# lab2_sokolov_boost.net
KiCad netlist of a schematic drawn in Altium Designer
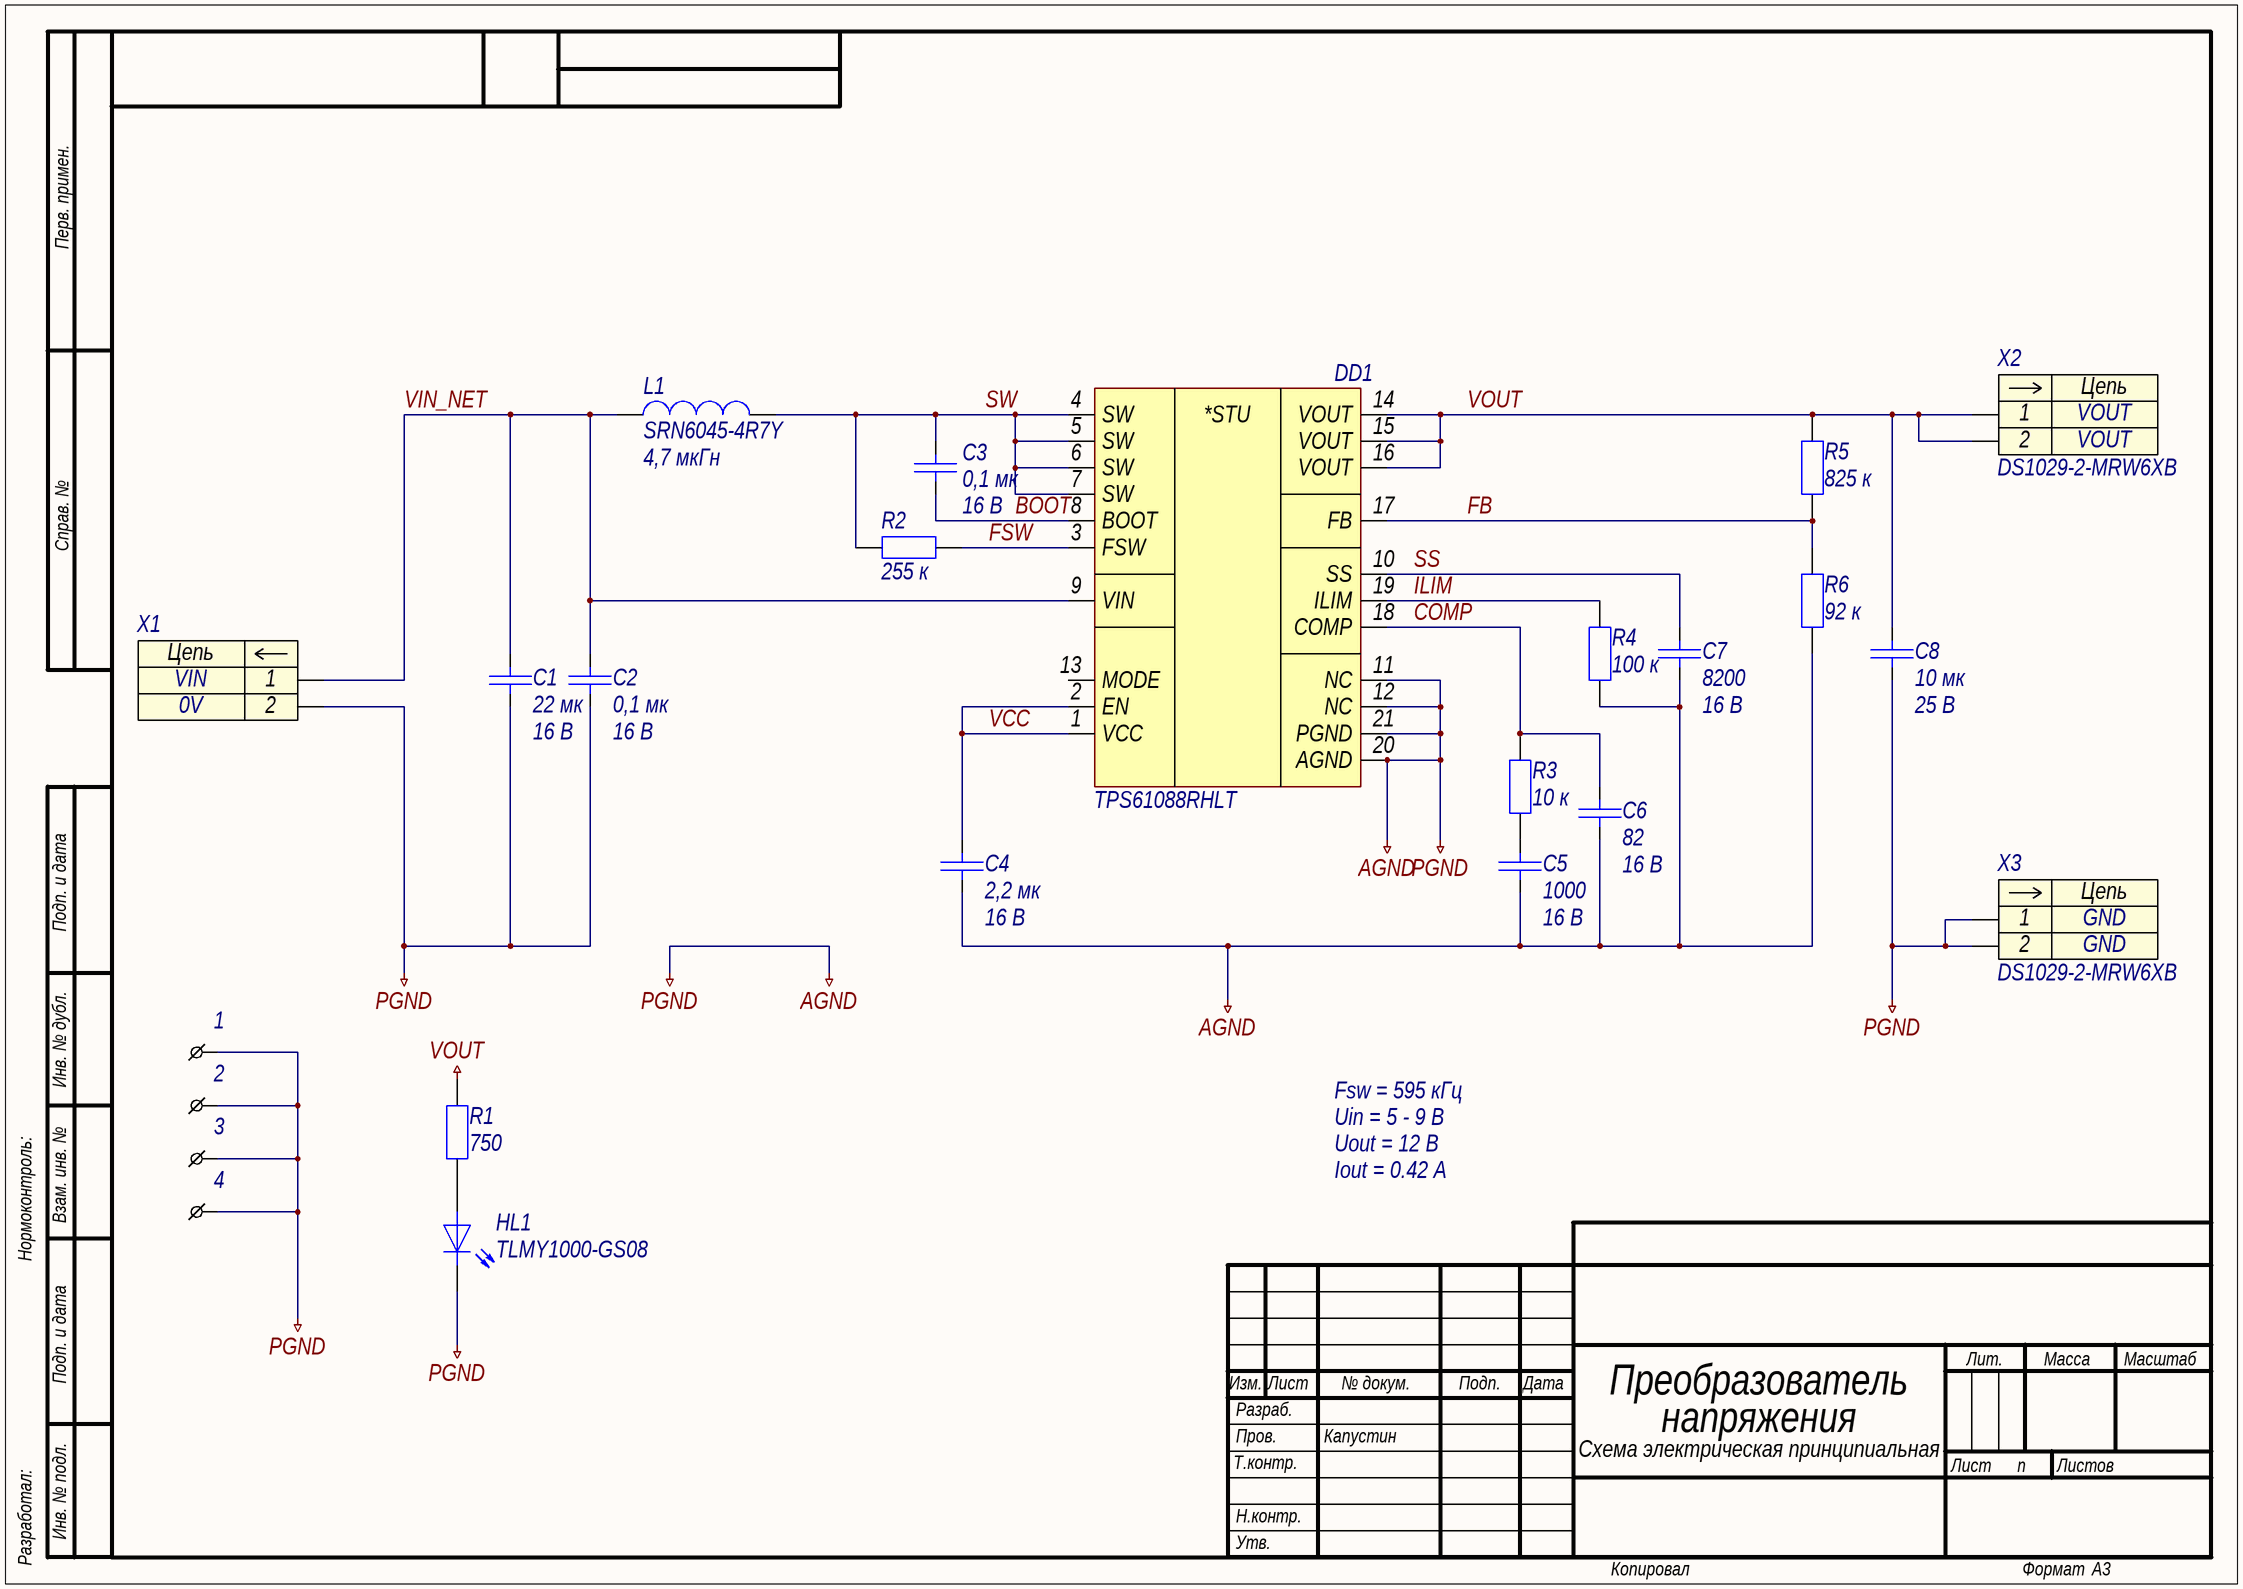
[diagram p0: lab2_sokolov_boost.SchDoc]

(export (version "E")
  (design (tool "Eeschema 10.0.6"))
  (components
    (comp (ref "1")
      (value "MOUNTING_HOLE")
      (footprint "HOLE_1,6X3,3")
      (libsource (lib "kravt_lib") (part "MOUNTING_HOLE"))
    )
    (comp (ref "2")
      (value "MOUNTING_HOLE")
      (footprint "HOLE_1,6X3,3")
      (libsource (lib "kravt_lib") (part "MOUNTING_HOLE"))
    )
    (comp (ref "3")
      (value "MOUNTING_HOLE")
      (footprint "HOLE_1,6X3,3")
      (libsource (lib "kravt_lib") (part "MOUNTING_HOLE"))
    )
    (comp (ref "4")
      (value "MOUNTING_HOLE")
      (footprint "HOLE_1,6X3,3")
      (libsource (lib "kravt_lib") (part "MOUNTING_HOLE"))
    )
    (comp (ref "C1")
      (value "22 мк")
      (footprint "C1206")
      (description "=Описание")
      (fields (field (name "НАПРЯЖЕНИЕ") "16 В"))
      (libsource (lib "Database_Students") (part "C-NONPOLAR"))
    )
    (comp (ref "C2")
      (value "0,1 мк")
      (footprint "C0402")
      (description "=Описание")
      (fields (field (name "НАПРЯЖЕНИЕ") "16 В"))
      (libsource (lib "Database_Students") (part "C-NONPOLAR"))
    )
    (comp (ref "C3")
      (value "0,1 мк")
      (footprint "C0402")
      (description "=Описание")
      (fields (field (name "НАПРЯЖЕНИЕ") "16 В"))
      (libsource (lib "Database_Students") (part "C-NONPOLAR"))
    )
    (comp (ref "C4")
      (value "2,2 мк")
      (footprint "C0603")
      (description "=Описание")
      (fields (field (name "НАПРЯЖЕНИЕ") "16 В"))
      (libsource (lib "Database_Students") (part "C-NONPOLAR"))
    )
    (comp (ref "C5")
      (value "1000")
      (footprint "C0201")
      (description "=Описание")
      (fields (field (name "НАПРЯЖЕНИЕ") "16 В"))
      (libsource (lib "Database_Students") (part "C-NONPOLAR"))
    )
    (comp (ref "C6")
      (value "82")
      (footprint "C0603")
      (description "=Описание")
      (fields (field (name "НАПРЯЖЕНИЕ") "16 В"))
      (libsource (lib "Database_Students") (part "C-NONPOLAR"))
    )
    (comp (ref "C7")
      (value "8200")
      (footprint "C0402")
      (description "=Описание")
      (fields (field (name "НАПРЯЖЕНИЕ") "16 В"))
      (libsource (lib "Database_Students") (part "C-NONPOLAR"))
    )
    (comp (ref "C8")
      (value "10 мк")
      (footprint "C0603")
      (description "=Описание")
      (fields (field (name "НАПРЯЖЕНИЕ") "25 В"))
      (libsource (lib "Database_Students") (part "C-NONPOLAR"))
    )
    (comp (ref "DD1")
      (value "TPS61088RHLT")
      (footprint "VQFN-20")
      (description "=Описание")
      (libsource (lib "Database_Students") (part "TPS61088RHLT"))
    )
    (comp (ref "HL1")
      (value "TLMY1000-GS08")
      (footprint "HL0603")
      (description "=Описание")
      (libsource (lib "Database_Students") (part "HL-COMMON"))
    )
    (comp (ref "L1")
      (value "SRN6045-4R7Y")
      (footprint "SRN-2-600X600X450")
      (description "=Описание")
      (fields (field (name "ИНДУКТИВНОСТЬ") "4,7 мкГн"))
      (libsource (lib "Database_Students") (part "INDUCTOR-COMMON"))
    )
    (comp (ref "R1")
      (value "750")
      (footprint "R0603")
      (description "=Описание")
      (libsource (lib "Database_Students") (part "R-COMMON"))
    )
    (comp (ref "R2")
      (value "255 к")
      (footprint "R0603")
      (description "=Описание")
      (libsource (lib "Database_Students") (part "R-COMMON"))
    )
    (comp (ref "R3")
      (value "10 к")
      (footprint "R0603")
      (description "=Описание")
      (libsource (lib "Database_Students") (part "R-COMMON"))
    )
    (comp (ref "R4")
      (value "100 к")
      (footprint "R0603")
      (description "=Описание")
      (libsource (lib "Database_Students") (part "R-COMMON"))
    )
    (comp (ref "R5")
      (value "825 к")
      (footprint "R0603")
      (description "=Описание")
      (libsource (lib "Database_Students") (part "R-COMMON"))
    )
    (comp (ref "R6")
      (value "92 к")
      (footprint "R0402")
      (description "=Описание")
      (libsource (lib "Database_Students") (part "R-COMMON"))
    )
    (comp (ref "X1")
      (value "~")
      (footprint "DS1029-2-MRW6XB")
      (description "=Описание")
      (libsource (lib "") (part "HEADER-2-PLG_1"))
    )
    (comp (ref "X2")
      (value "DS1029-2-MRW6XB")
      (footprint "DS1029-2-MRW6XB")
      (description "=Описание")
      (libsource (lib "Database_Students") (part "HEADER-2-PLG"))
    )
    (comp (ref "X3")
      (value "DS1029-2-MRW6XB")
      (footprint "DS1029-2-MRW6XB")
      (description "=Описание")
      (libsource (lib "Database_Students") (part "HEADER-2-PLG"))
    )
  )
  (nets
    (net (code "1") (name "/BOOT") (class "Default")
      (node (ref "C3") (pin "2") (pinfunction "2_2") (pintype "passive"))
      (node (ref "DD1") (pin "8") (pinfunction "BOOT_8") (pintype "passive"))
    )
    (net (code "2") (name "/COMP") (class "Default")
      (node (ref "C6") (pin "1") (pinfunction "1_1") (pintype "passive"))
      (node (ref "DD1") (pin "18") (pinfunction "COMP_18") (pintype "passive"))
      (node (ref "R3") (pin "1") (pinfunction "1_1") (pintype "passive"))
    )
    (net (code "3") (name "/FB") (class "Default")
      (node (ref "DD1") (pin "17") (pinfunction "FB_17") (pintype "passive"))
      (node (ref "R5") (pin "2") (pinfunction "2_2") (pintype "passive"))
      (node (ref "R6") (pin "1") (pinfunction "1_1") (pintype "passive"))
    )
    (net (code "4") (name "/FSW") (class "Default")
      (node (ref "DD1") (pin "3") (pinfunction "FSW_3") (pintype "passive"))
      (node (ref "R2") (pin "2") (pinfunction "2_2") (pintype "passive"))
    )
    (net (code "5") (name "/ILIM") (class "Default")
      (node (ref "DD1") (pin "19") (pinfunction "ILIM_19") (pintype "passive"))
      (node (ref "R4") (pin "1") (pinfunction "1_1") (pintype "passive"))
    )
    (net (code "6") (name "/SS") (class "Default")
      (node (ref "C7") (pin "2") (pinfunction "2_2") (pintype "passive"))
      (node (ref "DD1") (pin "10") (pinfunction "SS_10") (pintype "passive"))
    )
    (net (code "7") (name "/SW") (class "Default")
      (node (ref "C3") (pin "1") (pinfunction "1_1") (pintype "passive"))
      (node (ref "DD1") (pin "4") (pinfunction "SW_4") (pintype "passive"))
      (node (ref "DD1") (pin "5") (pinfunction "SW_5") (pintype "passive"))
      (node (ref "DD1") (pin "6") (pinfunction "SW_6") (pintype "passive"))
      (node (ref "DD1") (pin "7") (pinfunction "SW_7") (pintype "passive"))
      (node (ref "L1") (pin "2") (pinfunction "2_2") (pintype "passive"))
      (node (ref "R2") (pin "1") (pinfunction "1_1") (pintype "passive"))
    )
    (net (code "8") (name "/VCC") (class "Default")
      (node (ref "C4") (pin "2") (pinfunction "2_2") (pintype "passive"))
      (node (ref "DD1") (pin "1") (pinfunction "VCC_1") (pintype "passive"))
      (node (ref "DD1") (pin "2") (pinfunction "EN_2") (pintype "passive"))
    )
    (net (code "9") (name "/VIN_NET") (class "Default")
      (node (ref "C1") (pin "2") (pinfunction "2_2") (pintype "passive"))
      (node (ref "C2") (pin "2") (pinfunction "2_2") (pintype "passive"))
      (node (ref "DD1") (pin "9") (pinfunction "VIN_9") (pintype "passive"))
      (node (ref "L1") (pin "1") (pinfunction "1_1") (pintype "passive"))
      (node (ref "X1") (pin "1") (pinfunction "1_1") (pintype "passive"))
    )
    (net (code "10") (name "AGND") (class "Default")
      (node (ref "1") (pin "1") (pinfunction "1_1") (pintype "passive"))
      (node (ref "2") (pin "1") (pinfunction "1_1") (pintype "passive"))
      (node (ref "3") (pin "1") (pinfunction "1_1") (pintype "passive"))
      (node (ref "4") (pin "1") (pinfunction "1_1") (pintype "passive"))
      (node (ref "C1") (pin "1") (pinfunction "1_1") (pintype "passive"))
      (node (ref "C2") (pin "1") (pinfunction "1_1") (pintype "passive"))
      (node (ref "C4") (pin "1") (pinfunction "1_1") (pintype "passive"))
      (node (ref "C5") (pin "1") (pinfunction "1_1") (pintype "passive"))
      (node (ref "C6") (pin "2") (pinfunction "2_2") (pintype "passive"))
      (node (ref "C7") (pin "1") (pinfunction "1_1") (pintype "passive"))
      (node (ref "C8") (pin "1") (pinfunction "1_1") (pintype "passive"))
      (node (ref "DD1") (pin "11") (pinfunction "NC_11") (pintype "passive"))
      (node (ref "DD1") (pin "12") (pinfunction "NC_12") (pintype "passive"))
      (node (ref "DD1") (pin "20") (pinfunction "AGND_20") (pintype "passive"))
      (node (ref "DD1") (pin "21") (pinfunction "PGND_21") (pintype "passive"))
      (node (ref "HL1") (pin "1") (pinfunction "1_1") (pintype "passive"))
      (node (ref "R4") (pin "2") (pinfunction "2_2") (pintype "passive"))
      (node (ref "R6") (pin "2") (pinfunction "2_2") (pintype "passive"))
      (node (ref "X1") (pin "2") (pinfunction "2_2") (pintype "passive"))
      (node (ref "X3") (pin "1") (pinfunction "1_1") (pintype "passive"))
      (node (ref "X3") (pin "2") (pinfunction "2_2") (pintype "passive"))
    )
    (net (code "11") (name "Net-(C5-Pad2)") (class "Default")
      (node (ref "C5") (pin "2") (pinfunction "2_2") (pintype "passive"))
      (node (ref "R3") (pin "2") (pinfunction "2_2") (pintype "passive"))
    )
    (net (code "12") (name "Net-(HL1-Pad2)") (class "Default")
      (node (ref "HL1") (pin "2") (pinfunction "2_2") (pintype "passive"))
      (node (ref "R1") (pin "2") (pinfunction "2_2") (pintype "passive"))
    )
    (net (code "13") (name "VOUT") (class "Default")
      (node (ref "C8") (pin "2") (pinfunction "2_2") (pintype "passive"))
      (node (ref "DD1") (pin "14") (pinfunction "VOUT_14") (pintype "passive"))
      (node (ref "DD1") (pin "15") (pinfunction "VOUT_15") (pintype "passive"))
      (node (ref "DD1") (pin "16") (pinfunction "VOUT_16") (pintype "passive"))
      (node (ref "R1") (pin "1") (pinfunction "1_1") (pintype "passive"))
      (node (ref "R5") (pin "1") (pinfunction "1_1") (pintype "passive"))
      (node (ref "X2") (pin "1") (pinfunction "1_1") (pintype "passive"))
      (node (ref "X2") (pin "2") (pinfunction "2_2") (pintype "passive"))
    )
    (net (code "14") (name "unconnected-(DD1-MODE-Pad13)") (class "Default")
      (node (ref "DD1") (pin "13") (pinfunction "MODE_13") (pintype "passive"))
    )
  )
)
